# Transmitter_Power.net
KiCad netlist of a schematic drawn in Altium Designer
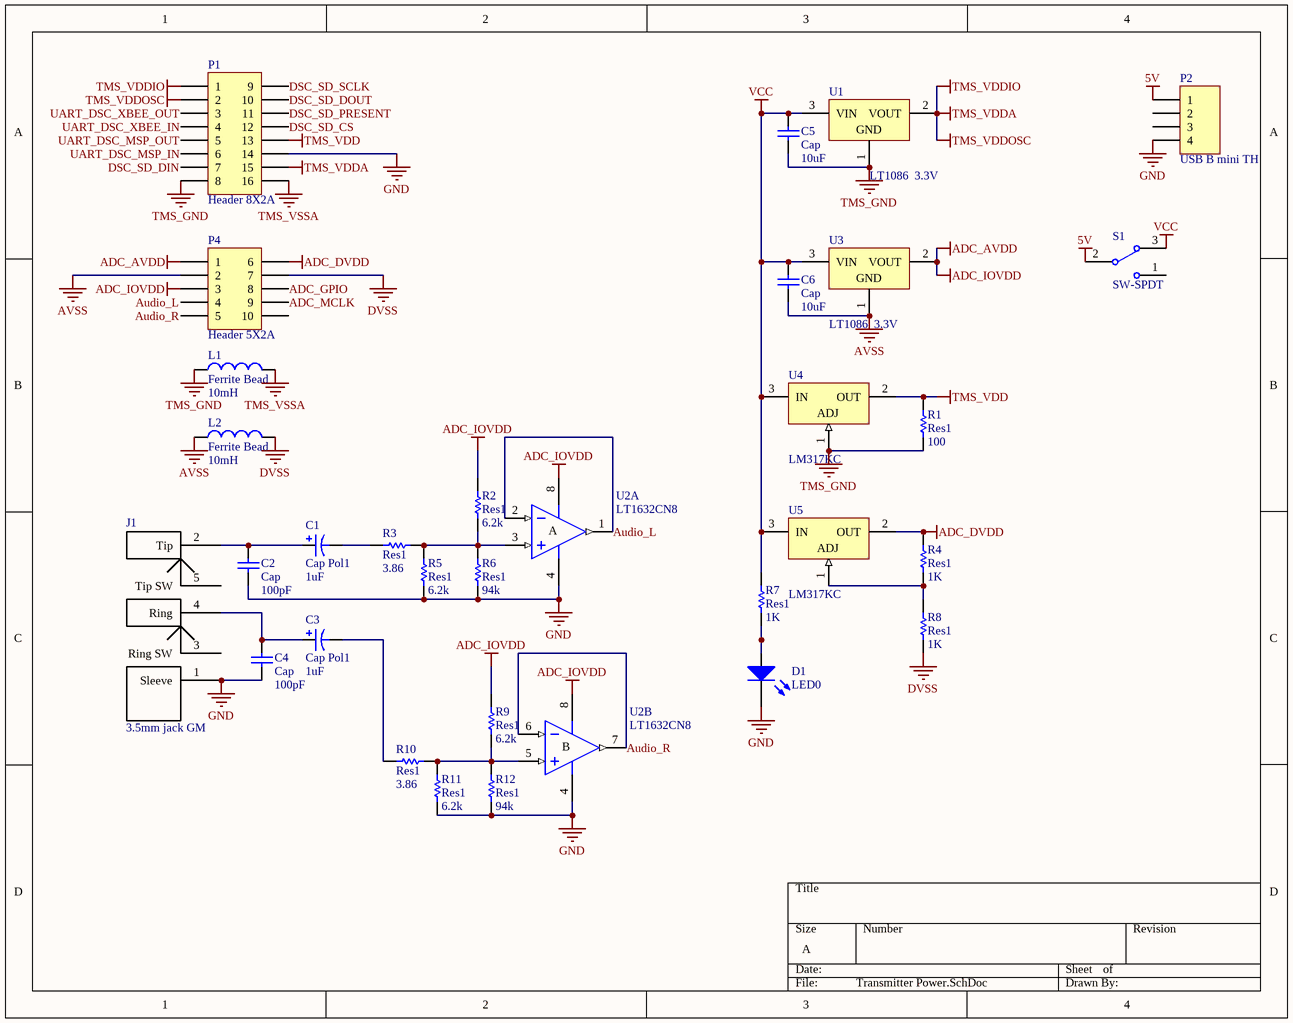
[diagram p0: Transmitter Power.SchDoc]

(export (version "E")
  (design (tool "Eeschema 10.0.6"))
  (components
    (comp (ref "C1")
      (value "Cap Pol1")
      (footprint "RB7.6-15")
      (description "Polarized Capacitor (Radial)")
      (fields (field (name "ALTIUM_VALUE") "1uF") (field (name "PUBLISHER") "Altium Limited"))
      (libsource (lib "Miscellaneous Devices") (part "Cap Pol1"))
    )
    (comp (ref "C2")
      (value "Cap")
      (footprint "RAD-0.3")
      (description "Capacitor")
      (fields (field (name "ALTIUM_VALUE") "100pF") (field (name "PUBLISHER") "Altium Limited"))
      (libsource (lib "Miscellaneous Devices") (part "Cap"))
    )
    (comp (ref "C3")
      (value "Cap Pol1")
      (footprint "RB7.6-15")
      (description "Polarized Capacitor (Radial)")
      (fields (field (name "ALTIUM_VALUE") "1uF") (field (name "PUBLISHER") "Altium Limited"))
      (libsource (lib "Miscellaneous Devices") (part "Cap Pol1"))
    )
    (comp (ref "C4")
      (value "Cap")
      (footprint "RAD-0.3")
      (description "Capacitor")
      (fields (field (name "ALTIUM_VALUE") "100pF") (field (name "PUBLISHER") "Altium Limited"))
      (libsource (lib "Miscellaneous Devices") (part "Cap"))
    )
    (comp (ref "C5")
      (value "Cap")
      (footprint "RAD-0.3")
      (description "Capacitor")
      (fields (field (name "ALTIUM_VALUE") "10uF") (field (name "PUBLISHER") "Altium Limited"))
      (libsource (lib "Miscellaneous Devices") (part "Cap"))
    )
    (comp (ref "C6")
      (value "Cap")
      (footprint "RAD-0.3")
      (description "Capacitor")
      (fields (field (name "ALTIUM_VALUE") "10uF") (field (name "PUBLISHER") "Altium Limited"))
      (libsource (lib "Miscellaneous Devices") (part "Cap"))
    )
    (comp (ref "D1")
      (value "LED0")
      (footprint "LED-0")
      (description "Typical INFRARED GaAs LED")
      (fields (field (name "PUBLISHER") "Altium Limited"))
      (libsource (lib "Miscellaneous Devices") (part "LED0"))
    )
    (comp (ref "J1")
      (value "3.5mm jack GM")
      (footprint "3.5mm jack GM")
      (libsource (lib "ECE LIB new") (part "3.5mm jack GM"))
    )
    (comp (ref "L1")
      (value "Ferrite Bead")
      (footprint "HDR1X2")
      (description "Inductor")
      (fields (field (name "ALTIUM_VALUE") "10mH") (field (name "PUBLISHER") "Altium Limited"))
      (libsource (lib "Miscellaneous Devices") (part "Inductor"))
    )
    (comp (ref "L2")
      (value "Ferrite Bead")
      (footprint "HDR1X2")
      (description "Inductor")
      (fields (field (name "ALTIUM_VALUE") "10mH") (field (name "PUBLISHER") "Altium Limited"))
      (libsource (lib "Miscellaneous Devices") (part "Inductor"))
    )
    (comp (ref "P1")
      (value "Header 8X2A")
      (footprint "HDR2X8_CEN")
      (description "Header, 8-Pin, Dual row")
      (fields (field (name "PUBLISHER") "Altium Limited"))
      (libsource (lib "Miscellaneous Connectors") (part "Header 8X2A"))
    )
    (comp (ref "P2")
      (value "USB B mini TH")
      (footprint "USB B mini Molex")
      (fields (field (name "PUBLISHER") "Altium Limited"))
      (libsource (lib "ECE LIB new") (part "USB B mini TH"))
    )
    (comp (ref "P4")
      (value "Header 5X2A")
      (footprint "HDR2X5_CEN")
      (description "Header, 5-Pin, Dual row")
      (fields (field (name "PUBLISHER") "Altium Limited"))
      (libsource (lib "Miscellaneous Connectors") (part "Header 5X2A"))
    )
    (comp (ref "R1")
      (value "Res1")
      (footprint "AXIAL-0.3")
      (description "Resistor")
      (fields (field (name "ALTIUM_VALUE") "100") (field (name "PUBLISHER") "Altium Limited"))
      (libsource (lib "Miscellaneous Devices") (part "Res1"))
    )
    (comp (ref "R2")
      (value "Res1")
      (footprint "AXIAL-0.3")
      (description "Resistor")
      (fields (field (name "ALTIUM_VALUE") "6.2k") (field (name "PUBLISHER") "Altium Limited"))
      (libsource (lib "Miscellaneous Devices") (part "Res1"))
    )
    (comp (ref "R3")
      (value "Res1")
      (footprint "AXIAL-0.3")
      (description "Resistor")
      (fields (field (name "ALTIUM_VALUE") "3.86") (field (name "PUBLISHER") "Altium Limited"))
      (libsource (lib "Miscellaneous Devices") (part "Res1"))
    )
    (comp (ref "R4")
      (value "Res1")
      (footprint "AXIAL-0.3")
      (description "Resistor")
      (fields (field (name "ALTIUM_VALUE") "1K") (field (name "PUBLISHER") "Altium Limited"))
      (libsource (lib "Miscellaneous Devices") (part "Res1"))
    )
    (comp (ref "R5")
      (value "Res1")
      (footprint "AXIAL-0.3")
      (description "Resistor")
      (fields (field (name "ALTIUM_VALUE") "6.2k") (field (name "PUBLISHER") "Altium Limited"))
      (libsource (lib "Miscellaneous Devices") (part "Res1"))
    )
    (comp (ref "R6")
      (value "Res1")
      (footprint "AXIAL-0.3")
      (description "Resistor")
      (fields (field (name "ALTIUM_VALUE") "94k") (field (name "PUBLISHER") "Altium Limited"))
      (libsource (lib "Miscellaneous Devices") (part "Res1"))
    )
    (comp (ref "R7")
      (value "Res1")
      (footprint "AXIAL-0.3")
      (description "Resistor")
      (fields (field (name "ALTIUM_VALUE") "1K") (field (name "PUBLISHER") "Altium Limited"))
      (libsource (lib "Miscellaneous Devices") (part "Res1"))
    )
    (comp (ref "R8")
      (value "Res1")
      (footprint "AXIAL-0.3")
      (description "Resistor")
      (fields (field (name "ALTIUM_VALUE") "1K") (field (name "PUBLISHER") "Altium Limited"))
      (libsource (lib "Miscellaneous Devices") (part "Res1"))
    )
    (comp (ref "R9")
      (value "Res1")
      (footprint "AXIAL-0.3")
      (description "Resistor")
      (fields (field (name "ALTIUM_VALUE") "6.2k") (field (name "PUBLISHER") "Altium Limited"))
      (libsource (lib "Miscellaneous Devices") (part "Res1"))
    )
    (comp (ref "R10")
      (value "Res1")
      (footprint "AXIAL-0.3")
      (description "Resistor")
      (fields (field (name "ALTIUM_VALUE") "3.86") (field (name "PUBLISHER") "Altium Limited"))
      (libsource (lib "Miscellaneous Devices") (part "Res1"))
    )
    (comp (ref "R11")
      (value "Res1")
      (footprint "AXIAL-0.3")
      (description "Resistor")
      (fields (field (name "ALTIUM_VALUE") "6.2k") (field (name "PUBLISHER") "Altium Limited"))
      (libsource (lib "Miscellaneous Devices") (part "Res1"))
    )
    (comp (ref "R12")
      (value "Res1")
      (footprint "AXIAL-0.3")
      (description "Resistor")
      (fields (field (name "ALTIUM_VALUE") "94k") (field (name "PUBLISHER") "Altium Limited"))
      (libsource (lib "Miscellaneous Devices") (part "Res1"))
    )
    (comp (ref "S1")
      (value "SW-SPDT")
      (footprint "SW DPST jameco")
      (description "SPDT Subminiature Toggle Switch, Right Angle Mounting, Vertical Actuation")
      (fields (field (name "PUBLISHER") "Altium Limited"))
      (libsource (lib "ECE LIB new") (part "SW-SPDT"))
    )
    (comp (ref "U1")
      (value "LT1086  3.3V")
      (footprint "TO-220")
      (libsource (lib "ECE LIB new") (part "LT1086  3.3V"))
    )
    (comp (ref "U2")
      (value "LT1632CN8")
      (footprint "DIP-8")
      (description "45MHz, 45V/µs, Dual Rail-to-Rail Input and Output Precision Operational Amplifier")
      (fields (field (name "PUBLISHER") "Altium Limited"))
      (libsource (lib "ECE LIB new") (part "LT1632CN8"))
    )
    (comp (ref "U3")
      (value "LT1086  3.3V")
      (footprint "TO-220")
      (libsource (lib "ECE LIB new") (part "LT1086  3.3V"))
    )
    (comp (ref "U4")
      (value "LM317KC")
      (footprint "KC03")
      (description "3-Terminal Adjustable Regulator")
      (fields (field (name "PUBLISHER") "Altium Limited"))
      (libsource (lib "TI Power Mgt Voltage Regulator") (part "LM317KC"))
    )
    (comp (ref "U5")
      (value "LM317KC")
      (footprint "KC03")
      (description "3-Terminal Adjustable Regulator")
      (fields (field (name "PUBLISHER") "Altium Limited"))
      (libsource (lib "TI Power Mgt Voltage Regulator") (part "LM317KC"))
    )
  )
  (nets
    (net (code "1") (name "/ADC_GPIO") (class "Default")
      (node (ref "P4") (pin "8") (pinfunction "8_8") (pintype "passive"))
    )
    (net (code "2") (name "/ADC_MCLK") (class "Default")
      (node (ref "P4") (pin "9") (pinfunction "9_9") (pintype "passive"))
    )
    (net (code "3") (name "/Audio_L") (class "Default")
      (node (ref "P4") (pin "4") (pinfunction "4_4") (pintype "passive"))
      (node (ref "U2") (pin "1") (pinfunction "OUT_1") (pintype "output"))
      (node (ref "U2") (pin "2") (pinfunction "IN-_2") (pintype "input"))
    )
    (net (code "4") (name "/Audio_R") (class "Default")
      (node (ref "P4") (pin "5") (pinfunction "5_5") (pintype "passive"))
      (node (ref "U2") (pin "6") (pinfunction "IN-_6") (pintype "input"))
      (node (ref "U2") (pin "7") (pinfunction "OUT_7") (pintype "output"))
    )
    (net (code "5") (name "/DSC_SD_CS") (class "Default")
      (node (ref "P1") (pin "12") (pinfunction "12_12") (pintype "passive"))
    )
    (net (code "6") (name "/DSC_SD_DIN") (class "Default")
      (node (ref "P1") (pin "7") (pinfunction "7_7") (pintype "passive"))
    )
    (net (code "7") (name "/DSC_SD_DOUT") (class "Default")
      (node (ref "P1") (pin "10") (pinfunction "10_10") (pintype "passive"))
    )
    (net (code "8") (name "/DSC_SD_PRESENT") (class "Default")
      (node (ref "P1") (pin "11") (pinfunction "11_11") (pintype "passive"))
    )
    (net (code "9") (name "/DSC_SD_SCLK") (class "Default")
      (node (ref "P1") (pin "9") (pinfunction "9_9") (pintype "passive"))
    )
    (net (code "10") (name "/UART_DSC_MSP_IN") (class "Default")
      (node (ref "P1") (pin "6") (pinfunction "6_6") (pintype "passive"))
    )
    (net (code "11") (name "/UART_DSC_MSP_OUT") (class "Default")
      (node (ref "P1") (pin "5") (pinfunction "5_5") (pintype "passive"))
    )
    (net (code "12") (name "/UART_DSC_XBEE_IN") (class "Default")
      (node (ref "P1") (pin "4") (pinfunction "4_4") (pintype "passive"))
    )
    (net (code "13") (name "/UART_DSC_XBEE_OUT") (class "Default")
      (node (ref "P1") (pin "3") (pinfunction "3_3") (pintype "passive"))
    )
    (net (code "14") (name "5V") (class "Default")
      (node (ref "P2") (pin "1") (pinfunction "1_1") (pintype "passive"))
      (node (ref "S1") (pin "2") (pinfunction "2_2") (pintype "passive"))
    )
    (net (code "15") (name "ADC_AVDD") (class "Default")
      (node (ref "P4") (pin "1") (pinfunction "1_1") (pintype "passive"))
      (node (ref "P4") (pin "3") (pinfunction "3_3") (pintype "passive"))
      (node (ref "R2") (pin "2") (pinfunction "2_2") (pintype "passive"))
      (node (ref "R9") (pin "2") (pinfunction "2_2") (pintype "passive"))
      (node (ref "U2") (pin "8") (pinfunction "V+_8") (pintype "power_in"))
      (node (ref "U3") (pin "2") (pinfunction "VOUT_2") (pintype "power_in"))
    )
    (net (code "16") (name "ADC_DVDD") (class "Default")
      (node (ref "P4") (pin "6") (pinfunction "6_6") (pintype "passive"))
      (node (ref "R4") (pin "2") (pinfunction "2_2") (pintype "passive"))
      (node (ref "U5") (pin "2") (pinfunction "OUT_2") (pintype "power_in"))
    )
    (net (code "17") (name "AVSS") (class "Default")
      (node (ref "C6") (pin "1") (pinfunction "1_1") (pintype "passive"))
      (node (ref "L2") (pin "1") (pinfunction "1_1") (pintype "passive"))
      (node (ref "P4") (pin "2") (pinfunction "2_2") (pintype "passive"))
      (node (ref "U3") (pin "1") (pinfunction "GND_1") (pintype "power_in"))
    )
    (net (code "18") (name "DVSS") (class "Default")
      (node (ref "L2") (pin "2") (pinfunction "2_2") (pintype "passive"))
      (node (ref "P4") (pin "7") (pinfunction "7_7") (pintype "passive"))
      (node (ref "R8") (pin "1") (pinfunction "1_1") (pintype "passive"))
    )
    (net (code "19") (name "GND") (class "Default")
      (node (ref "C2") (pin "1") (pinfunction "1_1") (pintype "passive"))
      (node (ref "C4") (pin "1") (pinfunction "1_1") (pintype "passive"))
      (node (ref "D1") (pin "2") (pinfunction "K_2") (pintype "passive"))
      (node (ref "J1") (pin "1") (pinfunction "Sleeve_1") (pintype "passive"))
      (node (ref "P1") (pin "14") (pinfunction "14_14") (pintype "passive"))
      (node (ref "P2") (pin "4") (pinfunction "4_4") (pintype "passive"))
      (node (ref "R11") (pin "1") (pinfunction "1_1") (pintype "passive"))
      (node (ref "R12") (pin "1") (pinfunction "1_1") (pintype "passive"))
      (node (ref "R5") (pin "1") (pinfunction "1_1") (pintype "passive"))
      (node (ref "R6") (pin "1") (pinfunction "1_1") (pintype "passive"))
      (node (ref "U2") (pin "4") (pinfunction "V-_4") (pintype "power_in"))
    )
    (net (code "20") (name "Net-(C1-Pad2)") (class "Default")
      (node (ref "C1") (pin "2") (pinfunction "2_2") (pintype "passive"))
      (node (ref "R3") (pin "1") (pinfunction "1_1") (pintype "passive"))
    )
    (net (code "21") (name "Net-(C3-Pad2)") (class "Default")
      (node (ref "C3") (pin "2") (pinfunction "2_2") (pintype "passive"))
      (node (ref "R10") (pin "1") (pinfunction "1_1") (pintype "passive"))
    )
    (net (code "22") (name "Net-(D1-A)") (class "Default")
      (node (ref "D1") (pin "1") (pinfunction "A_1") (pintype "passive"))
      (node (ref "R7") (pin "1") (pinfunction "1_1") (pintype "passive"))
    )
    (net (code "23") (name "Net-(J1-Ring)") (class "Default")
      (node (ref "C3") (pin "1") (pinfunction "1_1") (pintype "passive"))
      (node (ref "C4") (pin "2") (pinfunction "2_2") (pintype "passive"))
      (node (ref "J1") (pin "4") (pinfunction "Ring_4") (pintype "passive"))
    )
    (net (code "24") (name "Net-(J1-Tip)") (class "Default")
      (node (ref "C1") (pin "1") (pinfunction "1_1") (pintype "passive"))
      (node (ref "C2") (pin "2") (pinfunction "2_2") (pintype "passive"))
      (node (ref "J1") (pin "2") (pinfunction "Tip_2") (pintype "passive"))
    )
    (net (code "25") (name "Net-(U2A-IN+)") (class "Default")
      (node (ref "R2") (pin "1") (pinfunction "1_1") (pintype "passive"))
      (node (ref "R3") (pin "2") (pinfunction "2_2") (pintype "passive"))
      (node (ref "R5") (pin "2") (pinfunction "2_2") (pintype "passive"))
      (node (ref "R6") (pin "2") (pinfunction "2_2") (pintype "passive"))
      (node (ref "U2") (pin "3") (pinfunction "IN+_3") (pintype "input"))
    )
    (net (code "26") (name "Net-(U2B-IN+)") (class "Default")
      (node (ref "R10") (pin "2") (pinfunction "2_2") (pintype "passive"))
      (node (ref "R11") (pin "2") (pinfunction "2_2") (pintype "passive"))
      (node (ref "R12") (pin "2") (pinfunction "2_2") (pintype "passive"))
      (node (ref "R9") (pin "1") (pinfunction "1_1") (pintype "passive"))
      (node (ref "U2") (pin "5") (pinfunction "IN+_5") (pintype "input"))
    )
    (net (code "27") (name "Net-(U5-ADJ)") (class "Default")
      (node (ref "R4") (pin "1") (pinfunction "1_1") (pintype "passive"))
      (node (ref "R8") (pin "2") (pinfunction "2_2") (pintype "passive"))
      (node (ref "U5") (pin "1") (pinfunction "ADJ_1") (pintype "input"))
    )
    (net (code "28") (name "TMS_GND") (class "Default")
      (node (ref "C5") (pin "1") (pinfunction "1_1") (pintype "passive"))
      (node (ref "L1") (pin "1") (pinfunction "1_1") (pintype "passive"))
      (node (ref "P1") (pin "8") (pinfunction "8_8") (pintype "passive"))
      (node (ref "R1") (pin "1") (pinfunction "1_1") (pintype "passive"))
      (node (ref "U1") (pin "1") (pinfunction "GND_1") (pintype "power_in"))
      (node (ref "U4") (pin "1") (pinfunction "ADJ_1") (pintype "input"))
    )
    (net (code "29") (name "TMS_VDD") (class "Default")
      (node (ref "P1") (pin "13") (pinfunction "13_13") (pintype "passive"))
      (node (ref "R1") (pin "2") (pinfunction "2_2") (pintype "passive"))
      (node (ref "U4") (pin "2") (pinfunction "OUT_2") (pintype "power_in"))
    )
    (net (code "30") (name "TMS_VDDA") (class "Default")
      (node (ref "P1") (pin "1") (pinfunction "1_1") (pintype "passive"))
      (node (ref "P1") (pin "15") (pinfunction "15_15") (pintype "passive"))
      (node (ref "P1") (pin "2") (pinfunction "2_2") (pintype "passive"))
      (node (ref "U1") (pin "2") (pinfunction "VOUT_2") (pintype "power_in"))
    )
    (net (code "31") (name "TMS_VSSA") (class "Default")
      (node (ref "L1") (pin "2") (pinfunction "2_2") (pintype "passive"))
      (node (ref "P1") (pin "16") (pinfunction "16_16") (pintype "passive"))
    )
    (net (code "32") (name "VCC") (class "Default")
      (node (ref "C5") (pin "2") (pinfunction "2_2") (pintype "passive"))
      (node (ref "C6") (pin "2") (pinfunction "2_2") (pintype "passive"))
      (node (ref "R7") (pin "2") (pinfunction "2_2") (pintype "passive"))
      (node (ref "S1") (pin "3") (pinfunction "3_3") (pintype "passive"))
      (node (ref "U1") (pin "3") (pinfunction "VIN_3") (pintype "power_in"))
      (node (ref "U3") (pin "3") (pinfunction "VIN_3") (pintype "power_in"))
      (node (ref "U4") (pin "3") (pinfunction "IN_3") (pintype "power_in"))
      (node (ref "U5") (pin "3") (pinfunction "IN_3") (pintype "power_in"))
    )
    (net (code "33") (name "unconnected-(J1-Ring_SW-Pad3)") (class "Default")
      (node (ref "J1") (pin "3") (pinfunction "Ring_SW_3") (pintype "passive"))
    )
    (net (code "34") (name "unconnected-(J1-Tip_SW-Pad5)") (class "Default")
      (node (ref "J1") (pin "5") (pinfunction "Tip_SW_5") (pintype "passive"))
    )
    (net (code "35") (name "unconnected-(P2-Pad2)") (class "Default")
      (node (ref "P2") (pin "2") (pinfunction "2_2") (pintype "passive"))
    )
    (net (code "36") (name "unconnected-(P2-Pad3)") (class "Default")
      (node (ref "P2") (pin "3") (pinfunction "3_3") (pintype "passive"))
    )
    (net (code "37") (name "unconnected-(P4-Pad10)") (class "Default")
      (node (ref "P4") (pin "10") (pinfunction "10_10") (pintype "passive"))
    )
    (net (code "38") (name "unconnected-(S1-Pad1)") (class "Default")
      (node (ref "S1") (pin "1") (pinfunction "1_1") (pintype "passive"))
    )
  )
)
